# Omnimem.net
KiCad netlist of a schematic drawn in EAGLE
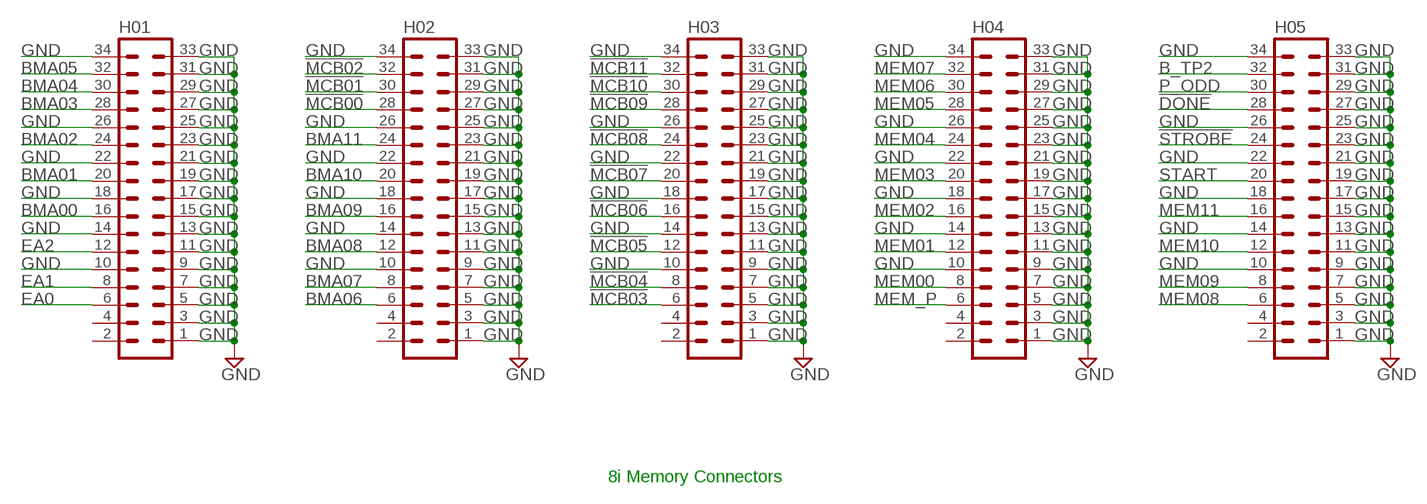
[diagram p0: schematic, sheet 1]
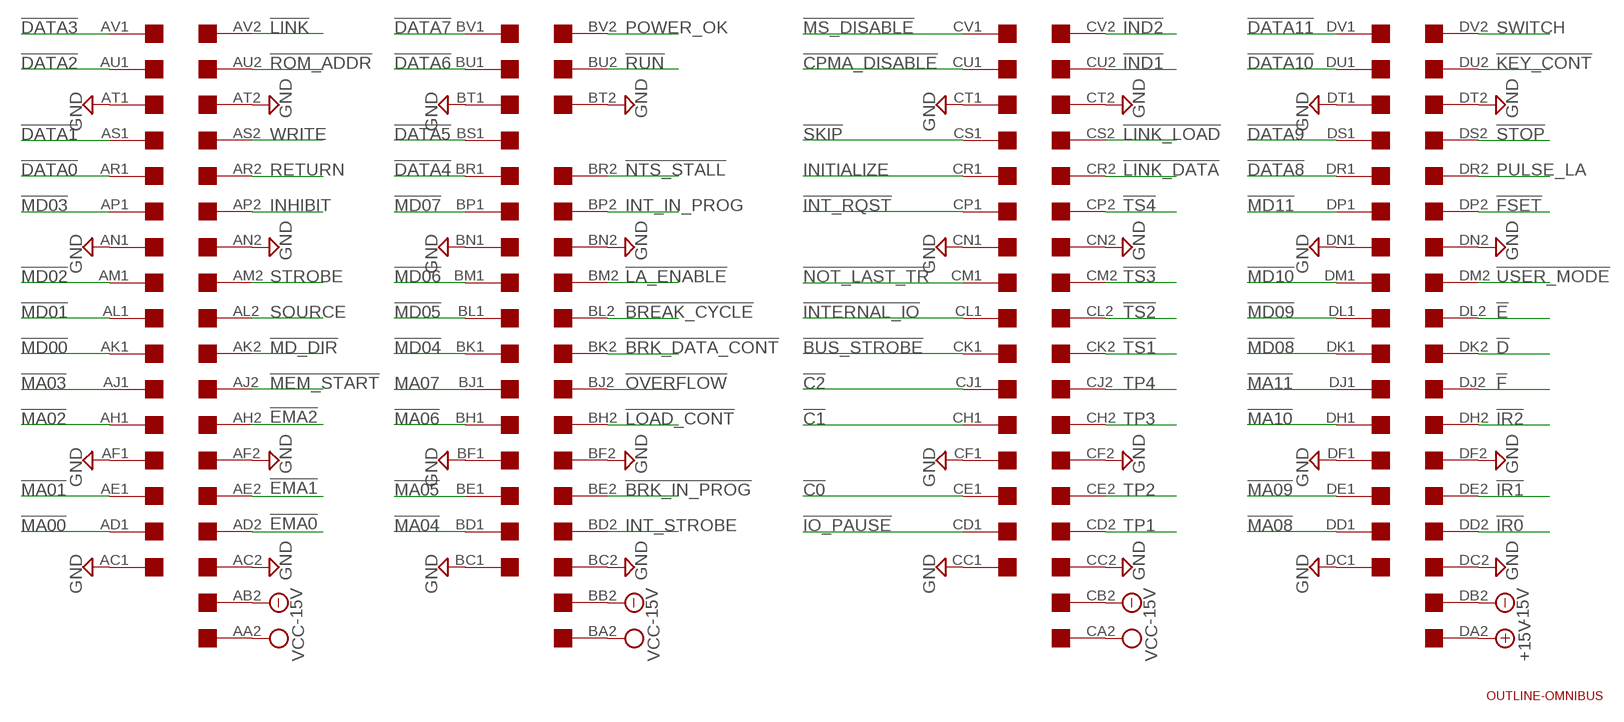
[diagram p1: schematic, sheet 2]
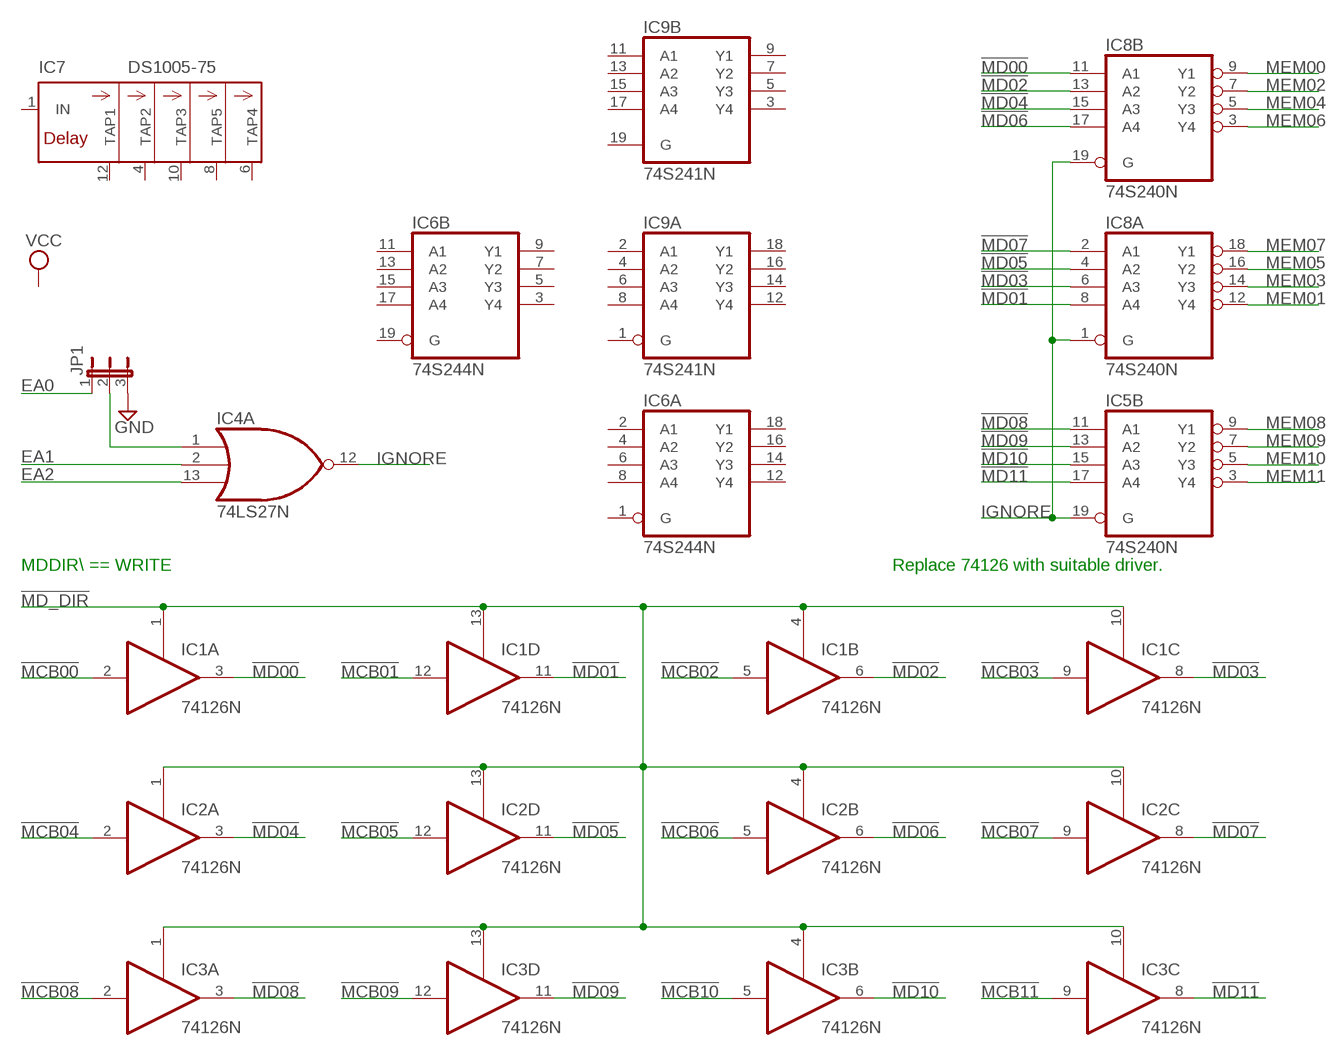
[diagram p2: schematic, sheet 3]
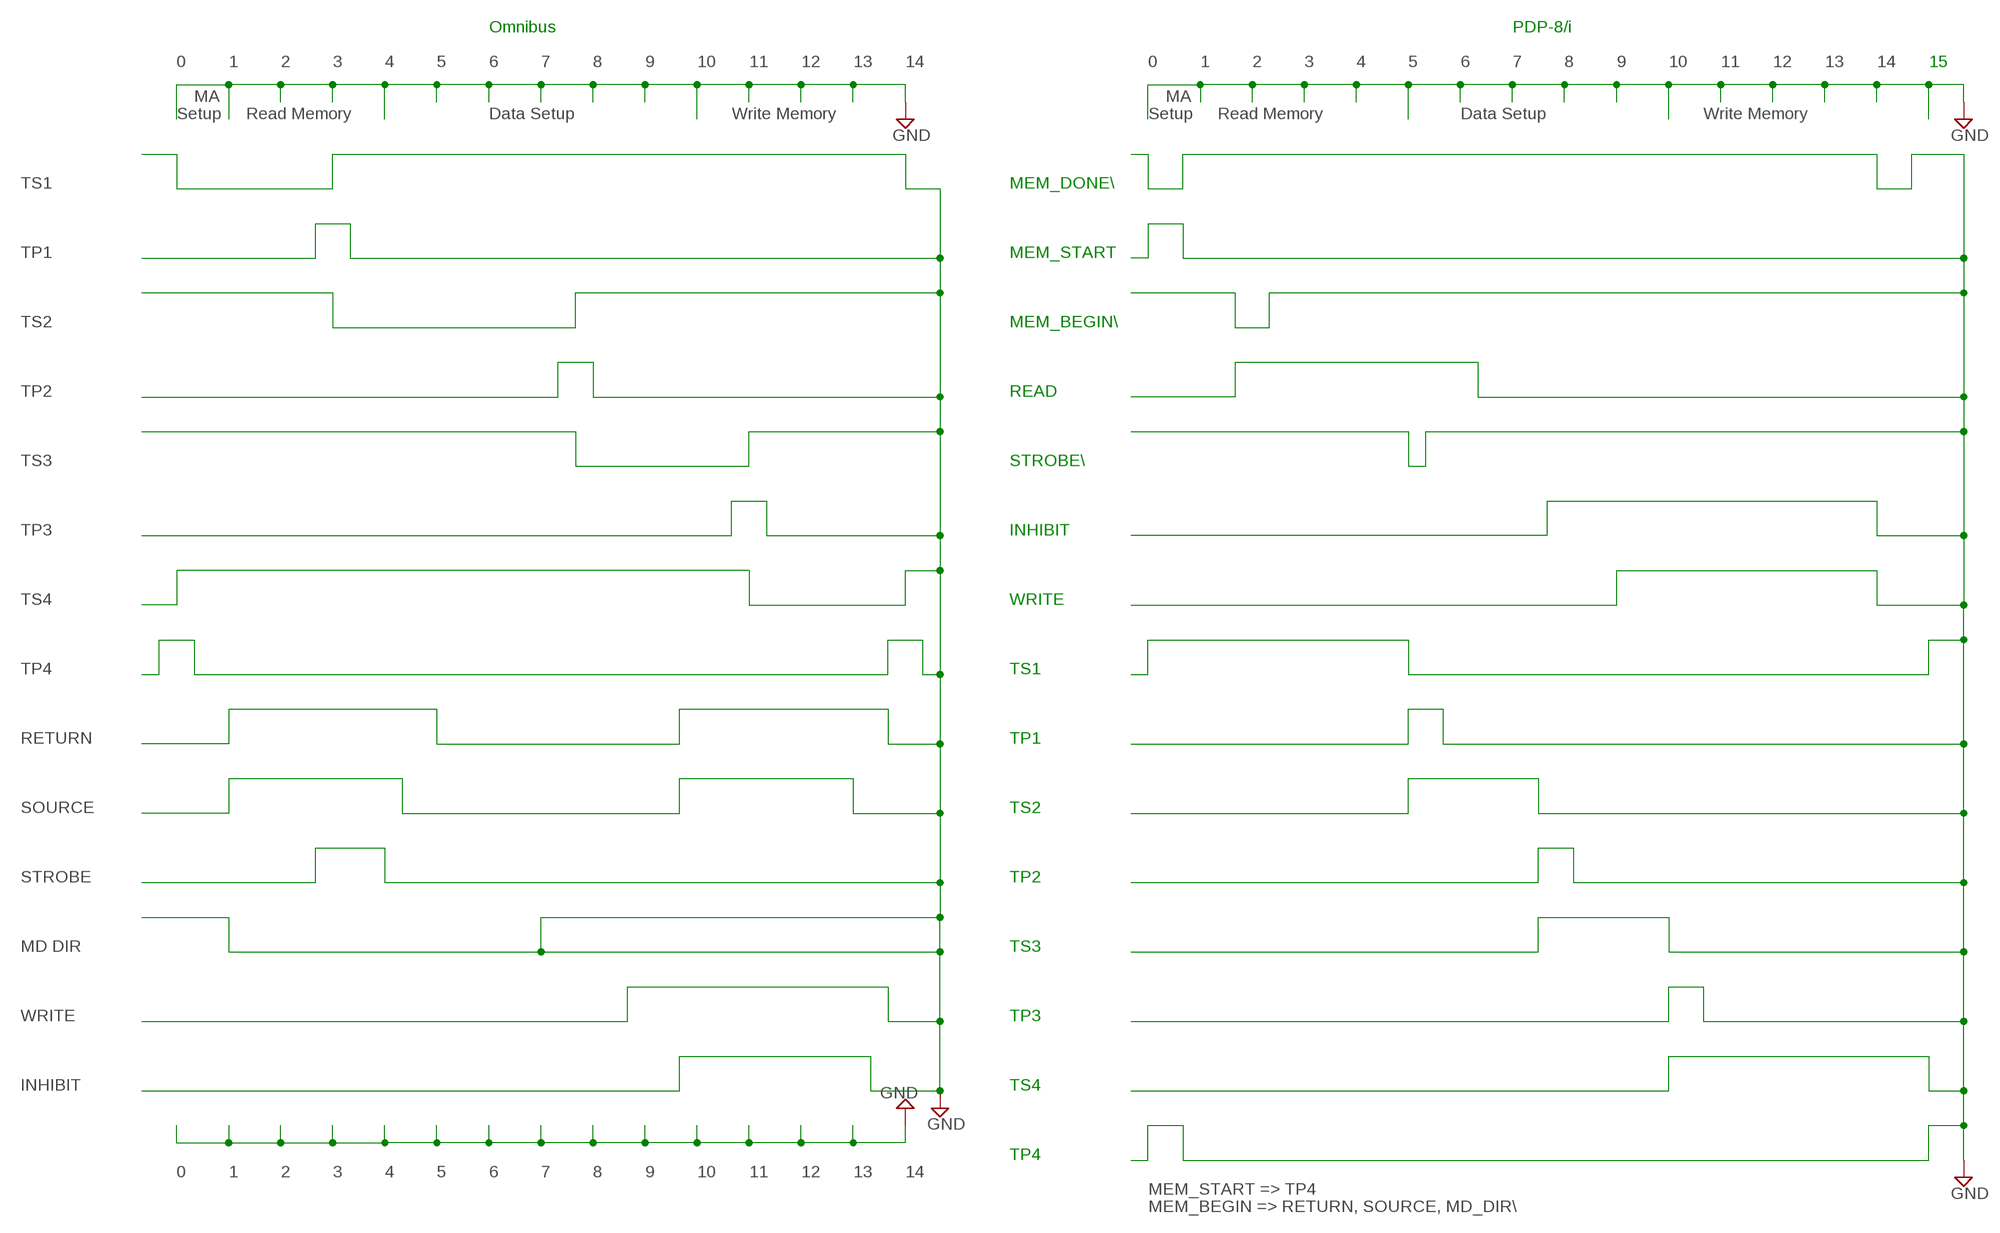
[diagram p3: schematic, sheet 4]

(export (version "E")
  (design (tool "Eeschema 10.0.6"))
  (components
    (comp (ref "H01")
      (value "MA17-2")
      (footprint "eagle-import:MA17-2")
      (libsource (lib "eagle-import") (part "MA17-2"))
    )
    (comp (ref "H02")
      (value "MA17-2")
      (footprint "eagle-import:MA17-2")
      (libsource (lib "eagle-import") (part "MA17-2"))
    )
    (comp (ref "H03")
      (value "MA17-2")
      (footprint "eagle-import:MA17-2")
      (libsource (lib "eagle-import") (part "MA17-2"))
    )
    (comp (ref "H04")
      (value "MA17-2")
      (footprint "eagle-import:MA17-2")
      (libsource (lib "eagle-import") (part "MA17-2"))
    )
    (comp (ref "H05")
      (value "MA17-2")
      (footprint "eagle-import:MA17-2")
      (libsource (lib "eagle-import") (part "MA17-2"))
    )
    (comp (ref "IC1")
      (value "74126N")
      (footprint "eagle-import:DIL14")
      (libsource (lib "eagle-import") (part "74126N"))
    )
    (comp (ref "IC2")
      (value "74126N")
      (footprint "eagle-import:DIL14")
      (libsource (lib "eagle-import") (part "74126N"))
    )
    (comp (ref "IC3")
      (value "74126N")
      (footprint "eagle-import:DIL14")
      (libsource (lib "eagle-import") (part "74126N"))
    )
    (comp (ref "IC4")
      (value "74LS27N")
      (footprint "eagle-import:DIL14")
      (libsource (lib "eagle-import") (part "7427NLS"))
    )
    (comp (ref "IC5")
      (value "74S240N")
      (footprint "eagle-import:DIL20")
      (libsource (lib "eagle-import") (part "74240NS"))
    )
    (comp (ref "IC6")
      (value "74S244N")
      (footprint "eagle-import:DIL20")
      (libsource (lib "eagle-import") (part "74244NS"))
    )
    (comp (ref "IC7")
      (value "DS1005-75")
      (footprint "eagle-import:DIL14")
      (libsource (lib "eagle-import") (part "MXD1000P"))
    )
    (comp (ref "IC8")
      (value "74S240N")
      (footprint "eagle-import:DIL20")
      (libsource (lib "eagle-import") (part "74240NS"))
    )
    (comp (ref "IC9")
      (value "74S241N")
      (footprint "eagle-import:DIL20")
      (libsource (lib "eagle-import") (part "74241NS"))
    )
    (comp (ref "JP1")
      (value "JP2E")
      (footprint "eagle-import:JP2")
      (libsource (lib "eagle-import") (part "JP2E"))
    )
    (comp (ref "U$1")
      (value "OUTLINE-OMNIBUS")
      (footprint "eagle-import:OMNIBUS")
      (libsource (lib "eagle-import") (part "OUTLINE-OMNIBUS"))
    )
    (comp (ref "U$2")
      (value "QUAD")
      (footprint "eagle-import:EDGE-CON8")
      (libsource (lib "eagle-import") (part "QUAD"))
    )
  )
  (nets
    (net (code "1") (name "+15V") (class "Default")
      (node (ref "U$2") (pin "DA2") (pinfunction "1_DA2") (pintype "bidirectional"))
    )
    (net (code "2") (name "-15V") (class "Default")
      (node (ref "U$2") (pin "AB2") (pinfunction "1_AB2") (pintype "bidirectional"))
      (node (ref "U$2") (pin "BB2") (pinfunction "1_BB2") (pintype "bidirectional"))
      (node (ref "U$2") (pin "CB2") (pinfunction "1_CB2") (pintype "bidirectional"))
      (node (ref "U$2") (pin "DB2") (pinfunction "1_DB2") (pintype "bidirectional"))
    )
    (net (code "3") (name "BMA00") (class "Default")
      (node (ref "H01") (pin "16") (pinfunction "16_16") (pintype "passive"))
    )
    (net (code "4") (name "BMA01") (class "Default")
      (node (ref "H01") (pin "20") (pinfunction "20_20") (pintype "passive"))
    )
    (net (code "5") (name "BMA02") (class "Default")
      (node (ref "H01") (pin "24") (pinfunction "24_24") (pintype "passive"))
    )
    (net (code "6") (name "BMA03") (class "Default")
      (node (ref "H01") (pin "28") (pinfunction "28_28") (pintype "passive"))
    )
    (net (code "7") (name "BMA04") (class "Default")
      (node (ref "H01") (pin "30") (pinfunction "30_30") (pintype "passive"))
    )
    (net (code "8") (name "BMA05") (class "Default")
      (node (ref "H01") (pin "32") (pinfunction "32_32") (pintype "passive"))
    )
    (net (code "9") (name "BMA06") (class "Default")
      (node (ref "H02") (pin "6") (pinfunction "6_6") (pintype "passive"))
    )
    (net (code "10") (name "BMA07") (class "Default")
      (node (ref "H02") (pin "8") (pinfunction "8_8") (pintype "passive"))
    )
    (net (code "11") (name "BMA08") (class "Default")
      (node (ref "H02") (pin "12") (pinfunction "12_12") (pintype "passive"))
    )
    (net (code "12") (name "BMA09") (class "Default")
      (node (ref "H02") (pin "16") (pinfunction "16_16") (pintype "passive"))
    )
    (net (code "13") (name "BMA10") (class "Default")
      (node (ref "H02") (pin "20") (pinfunction "20_20") (pintype "passive"))
    )
    (net (code "14") (name "BMA11") (class "Default")
      (node (ref "H02") (pin "24") (pinfunction "24_24") (pintype "passive"))
    )
    (net (code "15") (name "B_TP2") (class "Default")
      (node (ref "H05") (pin "32") (pinfunction "32_32") (pintype "passive"))
    )
    (net (code "16") (name "EA0") (class "Default")
      (node (ref "H01") (pin "6") (pinfunction "6_6") (pintype "passive"))
      (node (ref "JP1") (pin "1") (pinfunction "1_1") (pintype "passive"))
    )
    (net (code "17") (name "EA1") (class "Default")
      (node (ref "H01") (pin "8") (pinfunction "8_8") (pintype "passive"))
      (node (ref "IC4") (pin "2") (pinfunction "I1_2") (pintype "input"))
    )
    (net (code "18") (name "EA2") (class "Default")
      (node (ref "H01") (pin "12") (pinfunction "12_12") (pintype "passive"))
      (node (ref "IC4") (pin "13") (pinfunction "I2_13") (pintype "input"))
    )
    (net (code "19") (name "GND") (class "Default")
      (node (ref "H01") (pin "1") (pinfunction "1_1") (pintype "passive"))
      (node (ref "H01") (pin "10") (pinfunction "10_10") (pintype "passive"))
      (node (ref "H01") (pin "11") (pinfunction "11_11") (pintype "passive"))
      (node (ref "H01") (pin "13") (pinfunction "13_13") (pintype "passive"))
      (node (ref "H01") (pin "14") (pinfunction "14_14") (pintype "passive"))
      (node (ref "H01") (pin "15") (pinfunction "15_15") (pintype "passive"))
      (node (ref "H01") (pin "17") (pinfunction "17_17") (pintype "passive"))
      (node (ref "H01") (pin "18") (pinfunction "18_18") (pintype "passive"))
      (node (ref "H01") (pin "19") (pinfunction "19_19") (pintype "passive"))
      (node (ref "H01") (pin "21") (pinfunction "21_21") (pintype "passive"))
      (node (ref "H01") (pin "22") (pinfunction "22_22") (pintype "passive"))
      (node (ref "H01") (pin "23") (pinfunction "23_23") (pintype "passive"))
      (node (ref "H01") (pin "25") (pinfunction "25_25") (pintype "passive"))
      (node (ref "H01") (pin "26") (pinfunction "26_26") (pintype "passive"))
      (node (ref "H01") (pin "27") (pinfunction "27_27") (pintype "passive"))
      (node (ref "H01") (pin "29") (pinfunction "29_29") (pintype "passive"))
      (node (ref "H01") (pin "3") (pinfunction "3_3") (pintype "passive"))
      (node (ref "H01") (pin "31") (pinfunction "31_31") (pintype "passive"))
      (node (ref "H01") (pin "33") (pinfunction "33_33") (pintype "passive"))
      (node (ref "H01") (pin "34") (pinfunction "34_34") (pintype "passive"))
      (node (ref "H01") (pin "5") (pinfunction "5_5") (pintype "passive"))
      (node (ref "H01") (pin "7") (pinfunction "7_7") (pintype "passive"))
      (node (ref "H01") (pin "9") (pinfunction "9_9") (pintype "passive"))
      (node (ref "H02") (pin "1") (pinfunction "1_1") (pintype "passive"))
      (node (ref "H02") (pin "10") (pinfunction "10_10") (pintype "passive"))
      (node (ref "H02") (pin "11") (pinfunction "11_11") (pintype "passive"))
      (node (ref "H02") (pin "13") (pinfunction "13_13") (pintype "passive"))
      (node (ref "H02") (pin "14") (pinfunction "14_14") (pintype "passive"))
      (node (ref "H02") (pin "15") (pinfunction "15_15") (pintype "passive"))
      (node (ref "H02") (pin "17") (pinfunction "17_17") (pintype "passive"))
      (node (ref "H02") (pin "18") (pinfunction "18_18") (pintype "passive"))
      (node (ref "H02") (pin "19") (pinfunction "19_19") (pintype "passive"))
      (node (ref "H02") (pin "21") (pinfunction "21_21") (pintype "passive"))
      (node (ref "H02") (pin "22") (pinfunction "22_22") (pintype "passive"))
      (node (ref "H02") (pin "23") (pinfunction "23_23") (pintype "passive"))
      (node (ref "H02") (pin "25") (pinfunction "25_25") (pintype "passive"))
      (node (ref "H02") (pin "26") (pinfunction "26_26") (pintype "passive"))
      (node (ref "H02") (pin "27") (pinfunction "27_27") (pintype "passive"))
      (node (ref "H02") (pin "29") (pinfunction "29_29") (pintype "passive"))
      (node (ref "H02") (pin "3") (pinfunction "3_3") (pintype "passive"))
      (node (ref "H02") (pin "31") (pinfunction "31_31") (pintype "passive"))
      (node (ref "H02") (pin "33") (pinfunction "33_33") (pintype "passive"))
      (node (ref "H02") (pin "34") (pinfunction "34_34") (pintype "passive"))
      (node (ref "H02") (pin "5") (pinfunction "5_5") (pintype "passive"))
      (node (ref "H02") (pin "7") (pinfunction "7_7") (pintype "passive"))
      (node (ref "H02") (pin "9") (pinfunction "9_9") (pintype "passive"))
      (node (ref "H03") (pin "1") (pinfunction "1_1") (pintype "passive"))
      (node (ref "H03") (pin "10") (pinfunction "10_10") (pintype "passive"))
      (node (ref "H03") (pin "11") (pinfunction "11_11") (pintype "passive"))
      (node (ref "H03") (pin "13") (pinfunction "13_13") (pintype "passive"))
      (node (ref "H03") (pin "14") (pinfunction "14_14") (pintype "passive"))
      (node (ref "H03") (pin "15") (pinfunction "15_15") (pintype "passive"))
      (node (ref "H03") (pin "17") (pinfunction "17_17") (pintype "passive"))
      (node (ref "H03") (pin "18") (pinfunction "18_18") (pintype "passive"))
      (node (ref "H03") (pin "19") (pinfunction "19_19") (pintype "passive"))
      (node (ref "H03") (pin "21") (pinfunction "21_21") (pintype "passive"))
      (node (ref "H03") (pin "22") (pinfunction "22_22") (pintype "passive"))
      (node (ref "H03") (pin "23") (pinfunction "23_23") (pintype "passive"))
      (node (ref "H03") (pin "25") (pinfunction "25_25") (pintype "passive"))
      (node (ref "H03") (pin "26") (pinfunction "26_26") (pintype "passive"))
      (node (ref "H03") (pin "27") (pinfunction "27_27") (pintype "passive"))
      (node (ref "H03") (pin "29") (pinfunction "29_29") (pintype "passive"))
      (node (ref "H03") (pin "3") (pinfunction "3_3") (pintype "passive"))
      (node (ref "H03") (pin "31") (pinfunction "31_31") (pintype "passive"))
      (node (ref "H03") (pin "33") (pinfunction "33_33") (pintype "passive"))
      (node (ref "H03") (pin "34") (pinfunction "34_34") (pintype "passive"))
      (node (ref "H03") (pin "5") (pinfunction "5_5") (pintype "passive"))
      (node (ref "H03") (pin "7") (pinfunction "7_7") (pintype "passive"))
      (node (ref "H03") (pin "9") (pinfunction "9_9") (pintype "passive"))
      (node (ref "H04") (pin "1") (pinfunction "1_1") (pintype "passive"))
      (node (ref "H04") (pin "10") (pinfunction "10_10") (pintype "passive"))
      (node (ref "H04") (pin "11") (pinfunction "11_11") (pintype "passive"))
      (node (ref "H04") (pin "13") (pinfunction "13_13") (pintype "passive"))
      (node (ref "H04") (pin "14") (pinfunction "14_14") (pintype "passive"))
      (node (ref "H04") (pin "15") (pinfunction "15_15") (pintype "passive"))
      (node (ref "H04") (pin "17") (pinfunction "17_17") (pintype "passive"))
      (node (ref "H04") (pin "18") (pinfunction "18_18") (pintype "passive"))
      (node (ref "H04") (pin "19") (pinfunction "19_19") (pintype "passive"))
      (node (ref "H04") (pin "21") (pinfunction "21_21") (pintype "passive"))
      (node (ref "H04") (pin "22") (pinfunction "22_22") (pintype "passive"))
      (node (ref "H04") (pin "23") (pinfunction "23_23") (pintype "passive"))
      (node (ref "H04") (pin "25") (pinfunction "25_25") (pintype "passive"))
      (node (ref "H04") (pin "26") (pinfunction "26_26") (pintype "passive"))
      (node (ref "H04") (pin "27") (pinfunction "27_27") (pintype "passive"))
      (node (ref "H04") (pin "29") (pinfunction "29_29") (pintype "passive"))
      (node (ref "H04") (pin "3") (pinfunction "3_3") (pintype "passive"))
      (node (ref "H04") (pin "31") (pinfunction "31_31") (pintype "passive"))
      (node (ref "H04") (pin "33") (pinfunction "33_33") (pintype "passive"))
      (node (ref "H04") (pin "34") (pinfunction "34_34") (pintype "passive"))
      (node (ref "H04") (pin "5") (pinfunction "5_5") (pintype "passive"))
      (node (ref "H04") (pin "7") (pinfunction "7_7") (pintype "passive"))
      (node (ref "H04") (pin "9") (pinfunction "9_9") (pintype "passive"))
      (node (ref "H05") (pin "1") (pinfunction "1_1") (pintype "passive"))
      (node (ref "H05") (pin "10") (pinfunction "10_10") (pintype "passive"))
      (node (ref "H05") (pin "11") (pinfunction "11_11") (pintype "passive"))
      (node (ref "H05") (pin "13") (pinfunction "13_13") (pintype "passive"))
      (node (ref "H05") (pin "14") (pinfunction "14_14") (pintype "passive"))
      (node (ref "H05") (pin "15") (pinfunction "15_15") (pintype "passive"))
      (node (ref "H05") (pin "17") (pinfunction "17_17") (pintype "passive"))
      (node (ref "H05") (pin "18") (pinfunction "18_18") (pintype "passive"))
      (node (ref "H05") (pin "19") (pinfunction "19_19") (pintype "passive"))
      (node (ref "H05") (pin "21") (pinfunction "21_21") (pintype "passive"))
      (node (ref "H05") (pin "22") (pinfunction "22_22") (pintype "passive"))
      (node (ref "H05") (pin "23") (pinfunction "23_23") (pintype "passive"))
      (node (ref "H05") (pin "25") (pinfunction "25_25") (pintype "passive"))
      (node (ref "H05") (pin "26") (pinfunction "26_26") (pintype "passive"))
      (node (ref "H05") (pin "27") (pinfunction "27_27") (pintype "passive"))
      (node (ref "H05") (pin "29") (pinfunction "29_29") (pintype "passive"))
      (node (ref "H05") (pin "3") (pinfunction "3_3") (pintype "passive"))
      (node (ref "H05") (pin "31") (pinfunction "31_31") (pintype "passive"))
      (node (ref "H05") (pin "33") (pinfunction "33_33") (pintype "passive"))
      (node (ref "H05") (pin "34") (pinfunction "34_34") (pintype "passive"))
      (node (ref "H05") (pin "5") (pinfunction "5_5") (pintype "passive"))
      (node (ref "H05") (pin "7") (pinfunction "7_7") (pintype "passive"))
      (node (ref "H05") (pin "9") (pinfunction "9_9") (pintype "passive"))
      (node (ref "JP1") (pin "3") (pinfunction "3_3") (pintype "passive"))
      (node (ref "U$2") (pin "AC1") (pinfunction "1_AC1") (pintype "bidirectional"))
      (node (ref "U$2") (pin "AC2") (pinfunction "1_AC2") (pintype "bidirectional"))
      (node (ref "U$2") (pin "AF1") (pinfunction "1_AF1") (pintype "bidirectional"))
      (node (ref "U$2") (pin "AF2") (pinfunction "1_AF2") (pintype "bidirectional"))
      (node (ref "U$2") (pin "AN1") (pinfunction "1_AN1") (pintype "bidirectional"))
      (node (ref "U$2") (pin "AN2") (pinfunction "1_AN2") (pintype "bidirectional"))
      (node (ref "U$2") (pin "AT1") (pinfunction "1_AT1") (pintype "bidirectional"))
      (node (ref "U$2") (pin "AT2") (pinfunction "1_AT2") (pintype "bidirectional"))
      (node (ref "U$2") (pin "BC1") (pinfunction "1_BC1") (pintype "bidirectional"))
      (node (ref "U$2") (pin "BC2") (pinfunction "1_BC2") (pintype "bidirectional"))
      (node (ref "U$2") (pin "BF1") (pinfunction "1_BF1") (pintype "bidirectional"))
      (node (ref "U$2") (pin "BF2") (pinfunction "1_BF2") (pintype "bidirectional"))
      (node (ref "U$2") (pin "BN1") (pinfunction "1_BN1") (pintype "bidirectional"))
      (node (ref "U$2") (pin "BN2") (pinfunction "1_BN2") (pintype "bidirectional"))
      (node (ref "U$2") (pin "BT1") (pinfunction "1_BT1") (pintype "bidirectional"))
      (node (ref "U$2") (pin "BT2") (pinfunction "1_BT2") (pintype "bidirectional"))
      (node (ref "U$2") (pin "CC1") (pinfunction "1_CC1") (pintype "bidirectional"))
      (node (ref "U$2") (pin "CC2") (pinfunction "1_CC2") (pintype "bidirectional"))
      (node (ref "U$2") (pin "CF1") (pinfunction "1_CF1") (pintype "bidirectional"))
      (node (ref "U$2") (pin "CF2") (pinfunction "1_CF2") (pintype "bidirectional"))
      (node (ref "U$2") (pin "CN1") (pinfunction "1_CN1") (pintype "bidirectional"))
      (node (ref "U$2") (pin "CN2") (pinfunction "1_CN2") (pintype "bidirectional"))
      (node (ref "U$2") (pin "CT1") (pinfunction "1_CT1") (pintype "bidirectional"))
      (node (ref "U$2") (pin "CT2") (pinfunction "1_CT2") (pintype "bidirectional"))
      (node (ref "U$2") (pin "DC1") (pinfunction "1_DC1") (pintype "bidirectional"))
      (node (ref "U$2") (pin "DC2") (pinfunction "1_DC2") (pintype "bidirectional"))
      (node (ref "U$2") (pin "DF1") (pinfunction "1_DF1") (pintype "bidirectional"))
      (node (ref "U$2") (pin "DF2") (pinfunction "1_DF2") (pintype "bidirectional"))
      (node (ref "U$2") (pin "DN1") (pinfunction "1_DN1") (pintype "bidirectional"))
      (node (ref "U$2") (pin "DN2") (pinfunction "1_DN2") (pintype "bidirectional"))
      (node (ref "U$2") (pin "DT1") (pinfunction "1_DT1") (pintype "bidirectional"))
      (node (ref "U$2") (pin "DT2") (pinfunction "1_DT2") (pintype "bidirectional"))
    )
    (net (code "20") (name "IGNORE") (class "Default")
      (node (ref "IC4") (pin "12") (pinfunction "O_12") (pintype "output"))
      (node (ref "IC5") (pin "19") (pinfunction "G_19") (pintype "input"))
      (node (ref "IC8") (pin "1") (pinfunction "G_1") (pintype "input"))
      (node (ref "IC8") (pin "19") (pinfunction "G_19") (pintype "input"))
    )
    (net (code "21") (name "INHIBIT") (class "Default")
      (node (ref "U$2") (pin "AP2") (pinfunction "1_AP2") (pintype "bidirectional"))
    )
    (net (code "22") (name "INITIALIZE") (class "Default")
      (node (ref "U$2") (pin "CR1") (pinfunction "1_CR1") (pintype "bidirectional"))
    )
    (net (code "23") (name "INT_IN_PROG") (class "Default")
      (node (ref "U$2") (pin "BP2") (pinfunction "1_BP2") (pintype "bidirectional"))
    )
    (net (code "24") (name "INT_STROBE") (class "Default")
      (node (ref "U$2") (pin "BD2") (pinfunction "1_BD2") (pintype "bidirectional"))
    )
    (net (code "25") (name "MA07") (class "Default")
      (node (ref "U$2") (pin "BJ1") (pinfunction "1_BJ1") (pintype "bidirectional"))
    )
    (net (code "26") (name "MEM00") (class "Default")
      (node (ref "H04") (pin "8") (pinfunction "8_8") (pintype "passive"))
      (node (ref "IC8") (pin "9") (pinfunction "Y1_9") (pintype "tri_state"))
    )
    (net (code "27") (name "MEM01") (class "Default")
      (node (ref "H04") (pin "12") (pinfunction "12_12") (pintype "passive"))
      (node (ref "IC8") (pin "12") (pinfunction "Y4_12") (pintype "tri_state"))
    )
    (net (code "28") (name "MEM02") (class "Default")
      (node (ref "H04") (pin "16") (pinfunction "16_16") (pintype "passive"))
      (node (ref "IC8") (pin "7") (pinfunction "Y2_7") (pintype "tri_state"))
    )
    (net (code "29") (name "MEM03") (class "Default")
      (node (ref "H04") (pin "20") (pinfunction "20_20") (pintype "passive"))
      (node (ref "IC8") (pin "14") (pinfunction "Y3_14") (pintype "tri_state"))
    )
    (net (code "30") (name "MEM04") (class "Default")
      (node (ref "H04") (pin "24") (pinfunction "24_24") (pintype "passive"))
      (node (ref "IC8") (pin "5") (pinfunction "Y3_5") (pintype "tri_state"))
    )
    (net (code "31") (name "MEM05") (class "Default")
      (node (ref "H04") (pin "28") (pinfunction "28_28") (pintype "passive"))
      (node (ref "IC8") (pin "16") (pinfunction "Y2_16") (pintype "tri_state"))
    )
    (net (code "32") (name "MEM06") (class "Default")
      (node (ref "H04") (pin "30") (pinfunction "30_30") (pintype "passive"))
      (node (ref "IC8") (pin "3") (pinfunction "Y4_3") (pintype "tri_state"))
    )
    (net (code "33") (name "MEM07") (class "Default")
      (node (ref "H04") (pin "32") (pinfunction "32_32") (pintype "passive"))
      (node (ref "IC8") (pin "18") (pinfunction "Y1_18") (pintype "tri_state"))
    )
    (net (code "34") (name "MEM08") (class "Default")
      (node (ref "H05") (pin "6") (pinfunction "6_6") (pintype "passive"))
      (node (ref "IC5") (pin "9") (pinfunction "Y1_9") (pintype "tri_state"))
    )
    (net (code "35") (name "MEM09") (class "Default")
      (node (ref "H05") (pin "8") (pinfunction "8_8") (pintype "passive"))
      (node (ref "IC5") (pin "7") (pinfunction "Y2_7") (pintype "tri_state"))
    )
    (net (code "36") (name "MEM10") (class "Default")
      (node (ref "H05") (pin "12") (pinfunction "12_12") (pintype "passive"))
      (node (ref "IC5") (pin "5") (pinfunction "Y3_5") (pintype "tri_state"))
    )
    (net (code "37") (name "MEM11") (class "Default")
      (node (ref "H05") (pin "16") (pinfunction "16_16") (pintype "passive"))
      (node (ref "IC5") (pin "3") (pinfunction "Y4_3") (pintype "tri_state"))
    )
    (net (code "38") (name "MEM_P") (class "Default")
      (node (ref "H04") (pin "6") (pinfunction "6_6") (pintype "passive"))
    )
    (net (code "39") (name "Net-(IC4A-I0)") (class "Default")
      (node (ref "IC4") (pin "1") (pinfunction "I0_1") (pintype "input"))
      (node (ref "JP1") (pin "2") (pinfunction "2_2") (pintype "passive"))
    )
    (net (code "40") (name "POWER_OK") (class "Default")
      (node (ref "U$2") (pin "BV2") (pinfunction "1_BV2") (pintype "bidirectional"))
    )
    (net (code "41") (name "PULSE_LA") (class "Default")
      (node (ref "U$2") (pin "DR2") (pinfunction "1_DR2") (pintype "bidirectional"))
    )
    (net (code "42") (name "P_ODD") (class "Default")
      (node (ref "H05") (pin "30") (pinfunction "30_30") (pintype "passive"))
    )
    (net (code "43") (name "RETURN") (class "Default")
      (node (ref "U$2") (pin "AR2") (pinfunction "1_AR2") (pintype "bidirectional"))
    )
    (net (code "44") (name "SOURCE") (class "Default")
      (node (ref "U$2") (pin "AL2") (pinfunction "1_AL2") (pintype "bidirectional"))
    )
    (net (code "45") (name "START") (class "Default")
      (node (ref "H05") (pin "20") (pinfunction "20_20") (pintype "passive"))
    )
    (net (code "46") (name "STROBE") (class "Default")
      (node (ref "U$2") (pin "AM2") (pinfunction "1_AM2") (pintype "bidirectional"))
    )
    (net (code "47") (name "SWITCH") (class "Default")
      (node (ref "U$2") (pin "DV2") (pinfunction "1_DV2") (pintype "bidirectional"))
    )
    (net (code "48") (name "TP1") (class "Default")
      (node (ref "U$2") (pin "CD2") (pinfunction "1_CD2") (pintype "bidirectional"))
    )
    (net (code "49") (name "TP2") (class "Default")
      (node (ref "U$2") (pin "CE2") (pinfunction "1_CE2") (pintype "bidirectional"))
    )
    (net (code "50") (name "TP3") (class "Default")
      (node (ref "U$2") (pin "CH2") (pinfunction "1_CH2") (pintype "bidirectional"))
    )
    (net (code "51") (name "TP4") (class "Default")
      (node (ref "U$2") (pin "CJ2") (pinfunction "1_CJ2") (pintype "bidirectional"))
    )
    (net (code "52") (name "VCC") (class "Default")
      (node (ref "U$2") (pin "AA2") (pinfunction "1_AA2") (pintype "bidirectional"))
      (node (ref "U$2") (pin "BA2") (pinfunction "1_BA2") (pintype "bidirectional"))
      (node (ref "U$2") (pin "CA2") (pinfunction "1_CA2") (pintype "bidirectional"))
    )
    (net (code "53") (name "WRITE") (class "Default")
      (node (ref "U$2") (pin "AS2") (pinfunction "1_AS2") (pintype "bidirectional"))
    )
    (net (code "54") (name "unconnected-(H01-Pad2)") (class "Default")
      (node (ref "H01") (pin "2") (pinfunction "2_2") (pintype "passive"))
    )
    (net (code "55") (name "unconnected-(H01-Pad4)") (class "Default")
      (node (ref "H01") (pin "4") (pinfunction "4_4") (pintype "passive"))
    )
    (net (code "56") (name "unconnected-(H02-Pad2)") (class "Default")
      (node (ref "H02") (pin "2") (pinfunction "2_2") (pintype "passive"))
    )
    (net (code "57") (name "unconnected-(H02-Pad4)") (class "Default")
      (node (ref "H02") (pin "4") (pinfunction "4_4") (pintype "passive"))
    )
    (net (code "58") (name "unconnected-(H03-Pad2)") (class "Default")
      (node (ref "H03") (pin "2") (pinfunction "2_2") (pintype "passive"))
    )
    (net (code "59") (name "unconnected-(H03-Pad4)") (class "Default")
      (node (ref "H03") (pin "4") (pinfunction "4_4") (pintype "passive"))
    )
    (net (code "60") (name "unconnected-(H04-Pad2)") (class "Default")
      (node (ref "H04") (pin "2") (pinfunction "2_2") (pintype "passive"))
    )
    (net (code "61") (name "unconnected-(H04-Pad4)") (class "Default")
      (node (ref "H04") (pin "4") (pinfunction "4_4") (pintype "passive"))
    )
    (net (code "62") (name "unconnected-(H05-Pad2)") (class "Default")
      (node (ref "H05") (pin "2") (pinfunction "2_2") (pintype "passive"))
    )
    (net (code "63") (name "unconnected-(H05-Pad4)") (class "Default")
      (node (ref "H05") (pin "4") (pinfunction "4_4") (pintype "passive"))
    )
    (net (code "64") (name "unconnected-(IC6A-A1-Pad2)") (class "Default")
      (node (ref "IC6") (pin "2") (pinfunction "A1_2") (pintype "input"))
    )
    (net (code "65") (name "unconnected-(IC6A-A2-Pad4)") (class "Default")
      (node (ref "IC6") (pin "4") (pinfunction "A2_4") (pintype "input"))
    )
    (net (code "66") (name "unconnected-(IC6A-A3-Pad6)") (class "Default")
      (node (ref "IC6") (pin "6") (pinfunction "A3_6") (pintype "input"))
    )
    (net (code "67") (name "unconnected-(IC6A-A4-Pad8)") (class "Default")
      (node (ref "IC6") (pin "8") (pinfunction "A4_8") (pintype "input"))
    )
    (net (code "68") (name "unconnected-(IC6A-G-Pad1)") (class "Default")
      (node (ref "IC6") (pin "1") (pinfunction "G_1") (pintype "input"))
    )
    (net (code "69") (name "unconnected-(IC6A-Y1-Pad18)") (class "Default")
      (node (ref "IC6") (pin "18") (pinfunction "Y1_18") (pintype "tri_state"))
    )
    (net (code "70") (name "unconnected-(IC6A-Y2-Pad16)") (class "Default")
      (node (ref "IC6") (pin "16") (pinfunction "Y2_16") (pintype "tri_state"))
    )
    (net (code "71") (name "unconnected-(IC6A-Y3-Pad14)") (class "Default")
      (node (ref "IC6") (pin "14") (pinfunction "Y3_14") (pintype "tri_state"))
    )
    (net (code "72") (name "unconnected-(IC6A-Y4-Pad12)") (class "Default")
      (node (ref "IC6") (pin "12") (pinfunction "Y4_12") (pintype "tri_state"))
    )
    (net (code "73") (name "unconnected-(IC6B-A1-Pad11)") (class "Default")
      (node (ref "IC6") (pin "11") (pinfunction "A1_11") (pintype "input"))
    )
    (net (code "74") (name "unconnected-(IC6B-A2-Pad13)") (class "Default")
      (node (ref "IC6") (pin "13") (pinfunction "A2_13") (pintype "input"))
    )
    (net (code "75") (name "unconnected-(IC6B-A3-Pad15)") (class "Default")
      (node (ref "IC6") (pin "15") (pinfunction "A3_15") (pintype "input"))
    )
    (net (code "76") (name "unconnected-(IC6B-A4-Pad17)") (class "Default")
      (node (ref "IC6") (pin "17") (pinfunction "A4_17") (pintype "input"))
    )
    (net (code "77") (name "unconnected-(IC6B-G-Pad19)") (class "Default")
      (node (ref "IC6") (pin "19") (pinfunction "G_19") (pintype "input"))
    )
    (net (code "78") (name "unconnected-(IC6B-Y1-Pad9)") (class "Default")
      (node (ref "IC6") (pin "9") (pinfunction "Y1_9") (pintype "tri_state"))
    )
    (net (code "79") (name "unconnected-(IC6B-Y2-Pad7)") (class "Default")
      (node (ref "IC6") (pin "7") (pinfunction "Y2_7") (pintype "tri_state"))
    )
    (net (code "80") (name "unconnected-(IC6B-Y3-Pad5)") (class "Default")
      (node (ref "IC6") (pin "5") (pinfunction "Y3_5") (pintype "tri_state"))
    )
    (net (code "81") (name "unconnected-(IC6B-Y4-Pad3)") (class "Default")
      (node (ref "IC6") (pin "3") (pinfunction "Y4_3") (pintype "tri_state"))
    )
    (net (code "82") (name "unconnected-(IC7G-IN-Pad1)") (class "Default")
      (node (ref "IC7") (pin "1") (pinfunction "IN_1") (pintype "input"))
    )
    (net (code "83") (name "unconnected-(IC7G-TAP1-Pad12)") (class "Default")
      (node (ref "IC7") (pin "12") (pinfunction "TAP1_12") (pintype "output"))
    )
    (net (code "84") (name "unconnected-(IC7G-TAP2-Pad4)") (class "Default")
      (node (ref "IC7") (pin "4") (pinfunction "TAP2_4") (pintype "output"))
    )
    (net (code "85") (name "unconnected-(IC7G-TAP3-Pad10)") (class "Default")
      (node (ref "IC7") (pin "10") (pinfunction "TAP3_10") (pintype "output"))
    )
    (net (code "86") (name "unconnected-(IC7G-TAP4-Pad6)") (class "Default")
      (node (ref "IC7") (pin "6") (pinfunction "TAP4_6") (pintype "output"))
    )
    (net (code "87") (name "unconnected-(IC7G-TAP5-Pad8)") (class "Default")
      (node (ref "IC7") (pin "8") (pinfunction "TAP5_8") (pintype "output"))
    )
    (net (code "88") (name "unconnected-(IC9A-A1-Pad2)") (class "Default")
      (node (ref "IC9") (pin "2") (pinfunction "A1_2") (pintype "input"))
    )
    (net (code "89") (name "unconnected-(IC9A-A2-Pad4)") (class "Default")
      (node (ref "IC9") (pin "4") (pinfunction "A2_4") (pintype "input"))
    )
    (net (code "90") (name "unconnected-(IC9A-A3-Pad6)") (class "Default")
      (node (ref "IC9") (pin "6") (pinfunction "A3_6") (pintype "input"))
    )
    (net (code "91") (name "unconnected-(IC9A-A4-Pad8)") (class "Default")
      (node (ref "IC9") (pin "8") (pinfunction "A4_8") (pintype "input"))
    )
    (net (code "92") (name "unconnected-(IC9A-G-Pad1)") (class "Default")
      (node (ref "IC9") (pin "1") (pinfunction "G_1") (pintype "input"))
    )
    (net (code "93") (name "unconnected-(IC9A-Y1-Pad18)") (class "Default")
      (node (ref "IC9") (pin "18") (pinfunction "Y1_18") (pintype "tri_state"))
    )
    (net (code "94") (name "unconnected-(IC9A-Y2-Pad16)") (class "Default")
      (node (ref "IC9") (pin "16") (pinfunction "Y2_16") (pintype "tri_state"))
    )
    (net (code "95") (name "unconnected-(IC9A-Y3-Pad14)") (class "Default")
      (node (ref "IC9") (pin "14") (pinfunction "Y3_14") (pintype "tri_state"))
    )
    (net (code "96") (name "unconnected-(IC9A-Y4-Pad12)") (class "Default")
      (node (ref "IC9") (pin "12") (pinfunction "Y4_12") (pintype "tri_state"))
    )
    (net (code "97") (name "unconnected-(IC9B-A1-Pad11)") (class "Default")
      (node (ref "IC9") (pin "11") (pinfunction "A1_11") (pintype "input"))
    )
    (net (code "98") (name "unconnected-(IC9B-A2-Pad13)") (class "Default")
      (node (ref "IC9") (pin "13") (pinfunction "A2_13") (pintype "input"))
    )
    (net (code "99") (name "unconnected-(IC9B-A3-Pad15)") (class "Default")
      (node (ref "IC9") (pin "15") (pinfunction "A3_15") (pintype "input"))
    )
    (net (code "100") (name "unconnected-(IC9B-A4-Pad17)") (class "Default")
      (node (ref "IC9") (pin "17") (pinfunction "A4_17") (pintype "input"))
    )
    (net (code "101") (name "unconnected-(IC9B-G-Pad19)") (class "Default")
      (node (ref "IC9") (pin "19") (pinfunction "G_19") (pintype "input"))
    )
    (net (code "102") (name "unconnected-(IC9B-Y1-Pad9)") (class "Default")
      (node (ref "IC9") (pin "9") (pinfunction "Y1_9") (pintype "tri_state"))
    )
    (net (code "103") (name "unconnected-(IC9B-Y2-Pad7)") (class "Default")
      (node (ref "IC9") (pin "7") (pinfunction "Y2_7") (pintype "tri_state"))
    )
    (net (code "104") (name "unconnected-(IC9B-Y3-Pad5)") (class "Default")
      (node (ref "IC9") (pin "5") (pinfunction "Y3_5") (pintype "tri_state"))
    )
    (net (code "105") (name "unconnected-(IC9B-Y4-Pad3)") (class "Default")
      (node (ref "IC9") (pin "3") (pinfunction "Y4_3") (pintype "tri_state"))
    )
    (net (code "106") (name "~{BREAK_CYCLE}") (class "Default")
      (node (ref "U$2") (pin "BL2") (pinfunction "1_BL2") (pintype "bidirectional"))
    )
    (net (code "107") (name "~{BRK_DATA_CONT}") (class "Default")
      (node (ref "U$2") (pin "BK2") (pinfunction "1_BK2") (pintype "bidirectional"))
    )
    (net (code "108") (name "~{BRK_IN_PROG}") (class "Default")
      (node (ref "U$2") (pin "BE2") (pinfunction "1_BE2") (pintype "bidirectional"))
    )
    (net (code "109") (name "~{BUS_STROBE}") (class "Default")
      (node (ref "U$2") (pin "CK1") (pinfunction "1_CK1") (pintype "bidirectional"))
    )
    (net (code "110") (name "~{C0}") (class "Default")
      (node (ref "U$2") (pin "CE1") (pinfunction "1_CE1") (pintype "bidirectional"))
    )
    (net (code "111") (name "~{C1}") (class "Default")
      (node (ref "U$2") (pin "CH1") (pinfunction "1_CH1") (pintype "bidirectional"))
    )
    (net (code "112") (name "~{C2}") (class "Default")
      (node (ref "U$2") (pin "CJ1") (pinfunction "1_CJ1") (pintype "bidirectional"))
    )
    (net (code "113") (name "~{CPMA_DISABLE}") (class "Default")
      (node (ref "U$2") (pin "CU1") (pinfunction "1_CU1") (pintype "bidirectional"))
    )
    (net (code "114") (name "~{DATA0}") (class "Default")
      (node (ref "U$2") (pin "AR1") (pinfunction "1_AR1") (pintype "bidirectional"))
    )
    (net (code "115") (name "~{DATA1}") (class "Default")
      (node (ref "U$2") (pin "AS1") (pinfunction "1_AS1") (pintype "bidirectional"))
    )
    (net (code "116") (name "~{DATA2}") (class "Default")
      (node (ref "U$2") (pin "AU1") (pinfunction "1_AU1") (pintype "bidirectional"))
    )
    (net (code "117") (name "~{DATA3}") (class "Default")
      (node (ref "U$2") (pin "AV1") (pinfunction "1_AV1") (pintype "bidirectional"))
    )
    (net (code "118") (name "~{DATA4}") (class "Default")
      (node (ref "U$2") (pin "BR1") (pinfunction "1_BR1") (pintype "bidirectional"))
    )
    (net (code "119") (name "~{DATA5}") (class "Default")
      (node (ref "U$2") (pin "BS1") (pinfunction "1_BS1") (pintype "bidirectional"))
    )
    (net (code "120") (name "~{DATA6}") (class "Default")
      (node (ref "U$2") (pin "BU1") (pinfunction "1_BU1") (pintype "bidirectional"))
    )
    (net (code "121") (name "~{DATA7}") (class "Default")
      (node (ref "U$2") (pin "BV1") (pinfunction "1_BV1") (pintype "bidirectional"))
    )
    (net (code "122") (name "~{DATA8}") (class "Default")
      (node (ref "U$2") (pin "DR1") (pinfunction "1_DR1") (pintype "bidirectional"))
    )
    (net (code "123") (name "~{DATA9}") (class "Default")
      (node (ref "U$2") (pin "DS1") (pinfunction "1_DS1") (pintype "bidirectional"))
    )
    (net (code "124") (name "~{DATA10}") (class "Default")
      (node (ref "U$2") (pin "DU1") (pinfunction "1_DU1") (pintype "bidirectional"))
    )
    (net (code "125") (name "~{DATA11}") (class "Default")
      (node (ref "U$2") (pin "DV1") (pinfunction "1_DV1") (pintype "bidirectional"))
    )
    (net (code "126") (name "~{DONE}") (class "Default")
      (node (ref "H05") (pin "28") (pinfunction "28_28") (pintype "passive"))
    )
    (net (code "127") (name "~{D}") (class "Default")
      (node (ref "U$2") (pin "DK2") (pinfunction "1_DK2") (pintype "bidirectional"))
    )
    (net (code "128") (name "~{EMA0}") (class "Default")
      (node (ref "U$2") (pin "AD2") (pinfunction "1_AD2") (pintype "bidirectional"))
    )
    (net (code "129") (name "~{EMA1}") (class "Default")
      (node (ref "U$2") (pin "AE2") (pinfunction "1_AE2") (pintype "bidirectional"))
    )
    (net (code "130") (name "~{EMA2}") (class "Default")
      (node (ref "U$2") (pin "AH2") (pinfunction "1_AH2") (pintype "bidirectional"))
    )
    (net (code "131") (name "~{E}") (class "Default")
      (node (ref "U$2") (pin "DL2") (pinfunction "1_DL2") (pintype "bidirectional"))
    )
    (net (code "132") (name "~{FSET}") (class "Default")
      (node (ref "U$2") (pin "DP2") (pinfunction "1_DP2") (pintype "bidirectional"))
    )
    (net (code "133") (name "~{F}") (class "Default")
      (node (ref "U$2") (pin "DJ2") (pinfunction "1_DJ2") (pintype "bidirectional"))
    )
    (net (code "134") (name "~{IND1}") (class "Default")
      (node (ref "U$2") (pin "CU2") (pinfunction "1_CU2") (pintype "bidirectional"))
    )
    (net (code "135") (name "~{IND2}") (class "Default")
      (node (ref "U$2") (pin "CV2") (pinfunction "1_CV2") (pintype "bidirectional"))
    )
    (net (code "136") (name "~{INTERNAL_IO}") (class "Default")
      (node (ref "U$2") (pin "CL1") (pinfunction "1_CL1") (pintype "bidirectional"))
    )
    (net (code "137") (name "~{INT_RQST}") (class "Default")
      (node (ref "U$2") (pin "CP1") (pinfunction "1_CP1") (pintype "bidirectional"))
    )
    (net (code "138") (name "~{IO_PAUSE}") (class "Default")
      (node (ref "U$2") (pin "CD1") (pinfunction "1_CD1") (pintype "bidirectional"))
    )
    (net (code "139") (name "~{IR0}") (class "Default")
      (node (ref "U$2") (pin "DD2") (pinfunction "1_DD2") (pintype "bidirectional"))
    )
    (net (code "140") (name "~{IR1}") (class "Default")
      (node (ref "U$2") (pin "DE2") (pinfunction "1_DE2") (pintype "bidirectional"))
    )
    (net (code "141") (name "~{IR2}") (class "Default")
      (node (ref "U$2") (pin "DH2") (pinfunction "1_DH2") (pintype "bidirectional"))
    )
    (net (code "142") (name "~{KEY_CONT}") (class "Default")
      (node (ref "U$2") (pin "DU2") (pinfunction "1_DU2") (pintype "bidirectional"))
    )
    (net (code "143") (name "~{LA_ENABLE}") (class "Default")
      (node (ref "U$2") (pin "BM2") (pinfunction "1_BM2") (pintype "bidirectional"))
    )
    (net (code "144") (name "~{LINK_DATA}") (class "Default")
      (node (ref "U$2") (pin "CR2") (pinfunction "1_CR2") (pintype "bidirectional"))
    )
    (net (code "145") (name "~{LINK_LOAD}") (class "Default")
      (node (ref "U$2") (pin "CS2") (pinfunction "1_CS2") (pintype "bidirectional"))
    )
    (net (code "146") (name "~{LINK}") (class "Default")
      (node (ref "U$2") (pin "AV2") (pinfunction "1_AV2") (pintype "bidirectional"))
    )
    (net (code "147") (name "~{LOAD_CONT}") (class "Default")
      (node (ref "U$2") (pin "BH2") (pinfunction "1_BH2") (pintype "bidirectional"))
    )
    (net (code "148") (name "~{MA00}") (class "Default")
      (node (ref "U$2") (pin "AD1") (pinfunction "1_AD1") (pintype "bidirectional"))
    )
    (net (code "149") (name "~{MA01}") (class "Default")
      (node (ref "U$2") (pin "AE1") (pinfunction "1_AE1") (pintype "bidirectional"))
    )
    (net (code "150") (name "~{MA02}") (class "Default")
      (node (ref "U$2") (pin "AH1") (pinfunction "1_AH1") (pintype "bidirectional"))
    )
    (net (code "151") (name "~{MA03}") (class "Default")
      (node (ref "U$2") (pin "AJ1") (pinfunction "1_AJ1") (pintype "bidirectional"))
    )
    (net (code "152") (name "~{MA04}") (class "Default")
      (node (ref "U$2") (pin "BD1") (pinfunction "1_BD1") (pintype "bidirectional"))
    )
    (net (code "153") (name "~{MA05}") (class "Default")
      (node (ref "U$2") (pin "BE1") (pinfunction "1_BE1") (pintype "bidirectional"))
    )
    (net (code "154") (name "~{MA06}") (class "Default")
      (node (ref "U$2") (pin "BH1") (pinfunction "1_BH1") (pintype "bidirectional"))
    )
    (net (code "155") (name "~{MA08}") (class "Default")
      (node (ref "U$2") (pin "DD1") (pinfunction "1_DD1") (pintype "bidirectional"))
    )
    (net (code "156") (name "~{MA09}") (class "Default")
      (node (ref "U$2") (pin "DE1") (pinfunction "1_DE1") (pintype "bidirectional"))
    )
    (net (code "157") (name "~{MA10}") (class "Default")
      (node (ref "U$2") (pin "DH1") (pinfunction "1_DH1") (pintype "bidirectional"))
    )
    (net (code "158") (name "~{MA11}") (class "Default")
      (node (ref "U$2") (pin "DJ1") (pinfunction "1_DJ1") (pintype "bidirectional"))
    )
    (net (code "159") (name "~{MCB00}") (class "Default")
      (node (ref "H02") (pin "28") (pinfunction "28_28") (pintype "passive"))
      (node (ref "IC1") (pin "2") (pinfunction "I_2") (pintype "input"))
    )
    (net (code "160") (name "~{MCB01}") (class "Default")
      (node (ref "H02") (pin "30") (pinfunction "30_30") (pintype "passive"))
      (node (ref "IC1") (pin "12") (pinfunction "I_12") (pintype "input"))
    )
    (net (code "161") (name "~{MCB02}") (class "Default")
      (node (ref "H02") (pin "32") (pinfunction "32_32") (pintype "passive"))
      (node (ref "IC1") (pin "5") (pinfunction "I_5") (pintype "input"))
    )
    (net (code "162") (name "~{MCB03}") (class "Default")
      (node (ref "H03") (pin "6") (pinfunction "6_6") (pintype "passive"))
      (node (ref "IC1") (pin "9") (pinfunction "I_9") (pintype "input"))
    )
    (net (code "163") (name "~{MCB04}") (class "Default")
      (node (ref "H03") (pin "8") (pinfunction "8_8") (pintype "passive"))
      (node (ref "IC2") (pin "2") (pinfunction "I_2") (pintype "input"))
    )
    (net (code "164") (name "~{MCB05}") (class "Default")
      (node (ref "H03") (pin "12") (pinfunction "12_12") (pintype "passive"))
      (node (ref "IC2") (pin "12") (pinfunction "I_12") (pintype "input"))
    )
    (net (code "165") (name "~{MCB06}") (class "Default")
      (node (ref "H03") (pin "16") (pinfunction "16_16") (pintype "passive"))
      (node (ref "IC2") (pin "5") (pinfunction "I_5") (pintype "input"))
    )
    (net (code "166") (name "~{MCB07}") (class "Default")
      (node (ref "H03") (pin "20") (pinfunction "20_20") (pintype "passive"))
      (node (ref "IC2") (pin "9") (pinfunction "I_9") (pintype "input"))
    )
    (net (code "167") (name "~{MCB08}") (class "Default")
      (node (ref "H03") (pin "24") (pinfunction "24_24") (pintype "passive"))
      (node (ref "IC3") (pin "2") (pinfunction "I_2") (pintype "input"))
    )
    (net (code "168") (name "~{MCB09}") (class "Default")
      (node (ref "H03") (pin "28") (pinfunction "28_28") (pintype "passive"))
      (node (ref "IC3") (pin "12") (pinfunction "I_12") (pintype "input"))
    )
    (net (code "169") (name "~{MCB10}") (class "Default")
      (node (ref "H03") (pin "30") (pinfunction "30_30") (pintype "passive"))
      (node (ref "IC3") (pin "5") (pinfunction "I_5") (pintype "input"))
    )
    (net (code "170") (name "~{MCB11}") (class "Default")
      (node (ref "H03") (pin "32") (pinfunction "32_32") (pintype "passive"))
      (node (ref "IC3") (pin "9") (pinfunction "I_9") (pintype "input"))
    )
    (net (code "171") (name "~{MD00}") (class "Default")
      (node (ref "IC1") (pin "3") (pinfunction "O_3") (pintype "output"))
      (node (ref "IC8") (pin "11") (pinfunction "A1_11") (pintype "input"))
      (node (ref "U$2") (pin "AK1") (pinfunction "1_AK1") (pintype "bidirectional"))
    )
    (net (code "172") (name "~{MD01}") (class "Default")
      (node (ref "IC1") (pin "11") (pinfunction "O_11") (pintype "output"))
      (node (ref "IC8") (pin "8") (pinfunction "A4_8") (pintype "input"))
      (node (ref "U$2") (pin "AL1") (pinfunction "1_AL1") (pintype "bidirectional"))
    )
    (net (code "173") (name "~{MD02}") (class "Default")
      (node (ref "IC1") (pin "6") (pinfunction "O_6") (pintype "output"))
      (node (ref "IC8") (pin "13") (pinfunction "A2_13") (pintype "input"))
      (node (ref "U$2") (pin "AM1") (pinfunction "1_AM1") (pintype "bidirectional"))
    )
    (net (code "174") (name "~{MD03}") (class "Default")
      (node (ref "IC1") (pin "8") (pinfunction "O_8") (pintype "output"))
      (node (ref "IC8") (pin "6") (pinfunction "A3_6") (pintype "input"))
      (node (ref "U$2") (pin "AP1") (pinfunction "1_AP1") (pintype "bidirectional"))
    )
    (net (code "175") (name "~{MD04}") (class "Default")
      (node (ref "IC2") (pin "3") (pinfunction "O_3") (pintype "output"))
      (node (ref "IC8") (pin "15") (pinfunction "A3_15") (pintype "input"))
      (node (ref "U$2") (pin "BK1") (pinfunction "1_BK1") (pintype "bidirectional"))
    )
    (net (code "176") (name "~{MD05}") (class "Default")
      (node (ref "IC2") (pin "11") (pinfunction "O_11") (pintype "output"))
      (node (ref "IC8") (pin "4") (pinfunction "A2_4") (pintype "input"))
      (node (ref "U$2") (pin "BL1") (pinfunction "1_BL1") (pintype "bidirectional"))
    )
    (net (code "177") (name "~{MD06}") (class "Default")
      (node (ref "IC2") (pin "6") (pinfunction "O_6") (pintype "output"))
      (node (ref "IC8") (pin "17") (pinfunction "A4_17") (pintype "input"))
      (node (ref "U$2") (pin "BM1") (pinfunction "1_BM1") (pintype "bidirectional"))
    )
    (net (code "178") (name "~{MD07}") (class "Default")
      (node (ref "IC2") (pin "8") (pinfunction "O_8") (pintype "output"))
      (node (ref "IC8") (pin "2") (pinfunction "A1_2") (pintype "input"))
      (node (ref "U$2") (pin "BP1") (pinfunction "1_BP1") (pintype "bidirectional"))
    )
    (net (code "179") (name "~{MD08}") (class "Default")
      (node (ref "IC3") (pin "3") (pinfunction "O_3") (pintype "output"))
      (node (ref "IC5") (pin "11") (pinfunction "A1_11") (pintype "input"))
      (node (ref "U$2") (pin "DK1") (pinfunction "1_DK1") (pintype "bidirectional"))
    )
    (net (code "180") (name "~{MD09}") (class "Default")
      (node (ref "IC3") (pin "11") (pinfunction "O_11") (pintype "output"))
      (node (ref "IC5") (pin "13") (pinfunction "A2_13") (pintype "input"))
      (node (ref "U$2") (pin "DL1") (pinfunction "1_DL1") (pintype "bidirectional"))
    )
    (net (code "181") (name "~{MD10}") (class "Default")
      (node (ref "IC3") (pin "6") (pinfunction "O_6") (pintype "output"))
      (node (ref "IC5") (pin "15") (pinfunction "A3_15") (pintype "input"))
      (node (ref "U$2") (pin "DM1") (pinfunction "1_DM1") (pintype "bidirectional"))
    )
    (net (code "182") (name "~{MD11}") (class "Default")
      (node (ref "IC3") (pin "8") (pinfunction "O_8") (pintype "output"))
      (node (ref "IC5") (pin "17") (pinfunction "A4_17") (pintype "input"))
      (node (ref "U$2") (pin "DP1") (pinfunction "1_DP1") (pintype "bidirectional"))
    )
    (net (code "183") (name "~{MD_DIR}") (class "Default")
      (node (ref "IC1") (pin "1") (pinfunction "OE_1") (pintype "input"))
      (node (ref "IC1") (pin "10") (pinfunction "OE_10") (pintype "input"))
      (node (ref "IC1") (pin "13") (pinfunction "OE_13") (pintype "input"))
      (node (ref "IC1") (pin "4") (pinfunction "OE_4") (pintype "input"))
      (node (ref "IC2") (pin "1") (pinfunction "OE_1") (pintype "input"))
      (node (ref "IC2") (pin "10") (pinfunction "OE_10") (pintype "input"))
      (node (ref "IC2") (pin "13") (pinfunction "OE_13") (pintype "input"))
      (node (ref "IC2") (pin "4") (pinfunction "OE_4") (pintype "input"))
      (node (ref "IC3") (pin "1") (pinfunction "OE_1") (pintype "input"))
      (node (ref "IC3") (pin "10") (pinfunction "OE_10") (pintype "input"))
      (node (ref "IC3") (pin "13") (pinfunction "OE_13") (pintype "input"))
      (node (ref "IC3") (pin "4") (pinfunction "OE_4") (pintype "input"))
      (node (ref "U$2") (pin "AK2") (pinfunction "1_AK2") (pintype "bidirectional"))
    )
    (net (code "184") (name "~{MEM_START}") (class "Default")
      (node (ref "U$2") (pin "AJ2") (pinfunction "1_AJ2") (pintype "bidirectional"))
    )
    (net (code "185") (name "~{MS_DISABLE}") (class "Default")
      (node (ref "U$2") (pin "CV1") (pinfunction "1_CV1") (pintype "bidirectional"))
    )
    (net (code "186") (name "~{NOT_LAST_TR}") (class "Default")
      (node (ref "U$2") (pin "CM1") (pinfunction "1_CM1") (pintype "bidirectional"))
    )
    (net (code "187") (name "~{NTS_STALL}") (class "Default")
      (node (ref "U$2") (pin "BR2") (pinfunction "1_BR2") (pintype "bidirectional"))
    )
    (net (code "188") (name "~{OVERFLOW}") (class "Default")
      (node (ref "U$2") (pin "BJ2") (pinfunction "1_BJ2") (pintype "bidirectional"))
    )
    (net (code "189") (name "~{ROM_ADDR}") (class "Default")
      (node (ref "U$2") (pin "AU2") (pinfunction "1_AU2") (pintype "bidirectional"))
    )
    (net (code "190") (name "~{RUN}") (class "Default")
      (node (ref "U$2") (pin "BU2") (pinfunction "1_BU2") (pintype "bidirectional"))
    )
    (net (code "191") (name "~{SKIP}") (class "Default")
      (node (ref "U$2") (pin "CS1") (pinfunction "1_CS1") (pintype "bidirectional"))
    )
    (net (code "192") (name "~{STOP}") (class "Default")
      (node (ref "U$2") (pin "DS2") (pinfunction "1_DS2") (pintype "bidirectional"))
    )
    (net (code "193") (name "~{STROBE}") (class "Default")
      (node (ref "H05") (pin "24") (pinfunction "24_24") (pintype "passive"))
    )
    (net (code "194") (name "~{TS1}") (class "Default")
      (node (ref "U$2") (pin "CK2") (pinfunction "1_CK2") (pintype "bidirectional"))
    )
    (net (code "195") (name "~{TS2}") (class "Default")
      (node (ref "U$2") (pin "CL2") (pinfunction "1_CL2") (pintype "bidirectional"))
    )
    (net (code "196") (name "~{TS3}") (class "Default")
      (node (ref "U$2") (pin "CM2") (pinfunction "1_CM2") (pintype "bidirectional"))
    )
    (net (code "197") (name "~{TS4}") (class "Default")
      (node (ref "U$2") (pin "CP2") (pinfunction "1_CP2") (pintype "bidirectional"))
    )
    (net (code "198") (name "~{USER_MODE}") (class "Default")
      (node (ref "U$2") (pin "DM2") (pinfunction "1_DM2") (pintype "bidirectional"))
    )
  )
)
